# schematic.net
KiCad netlist of a schematic drawn in EAGLE
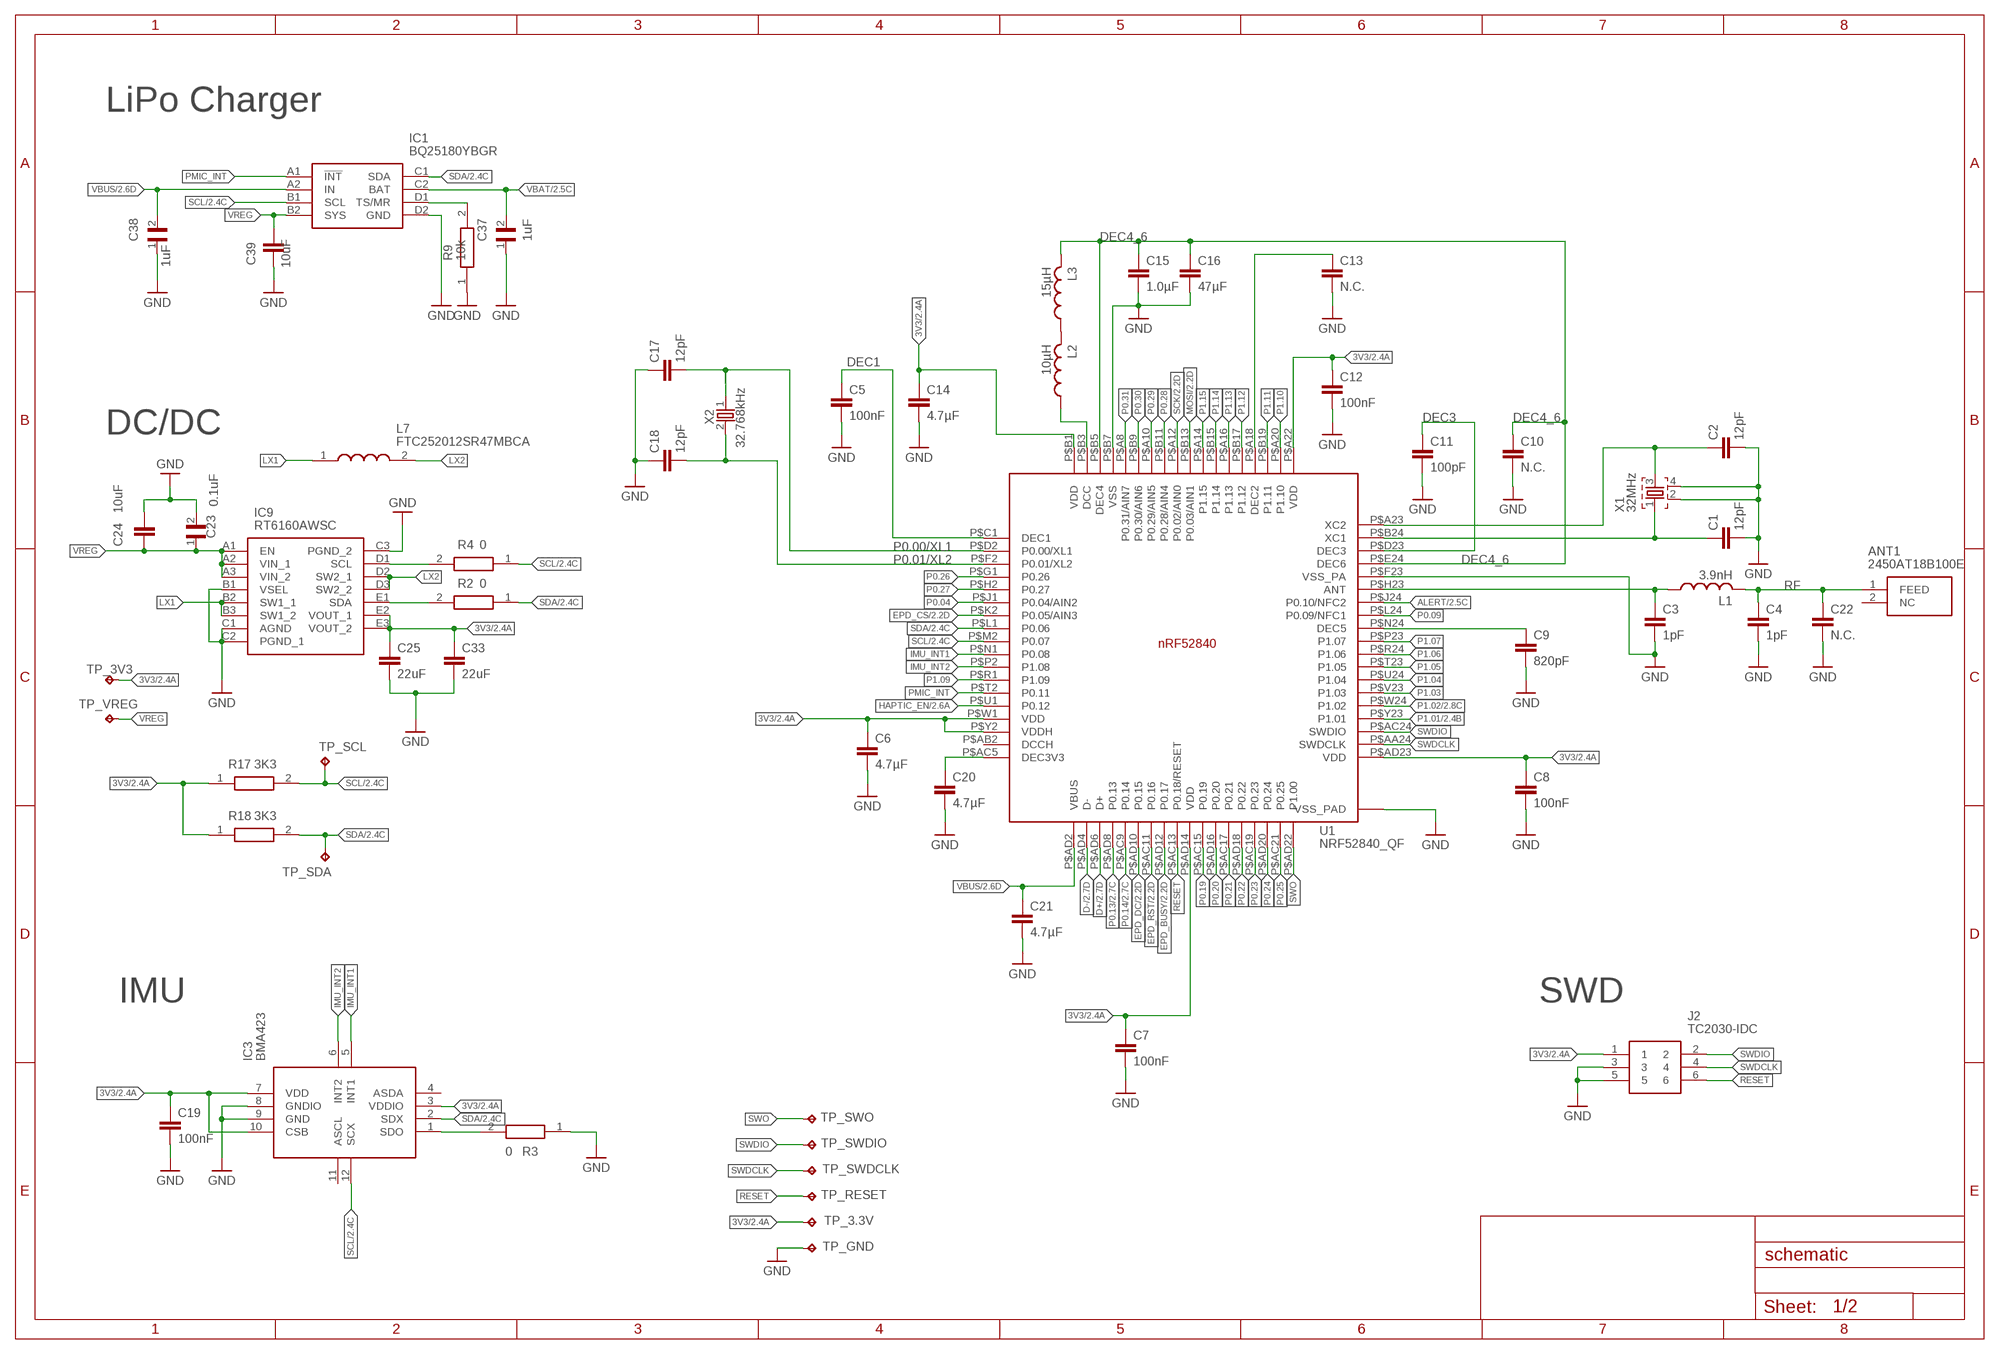
[diagram p0: schematic, sheet 1]
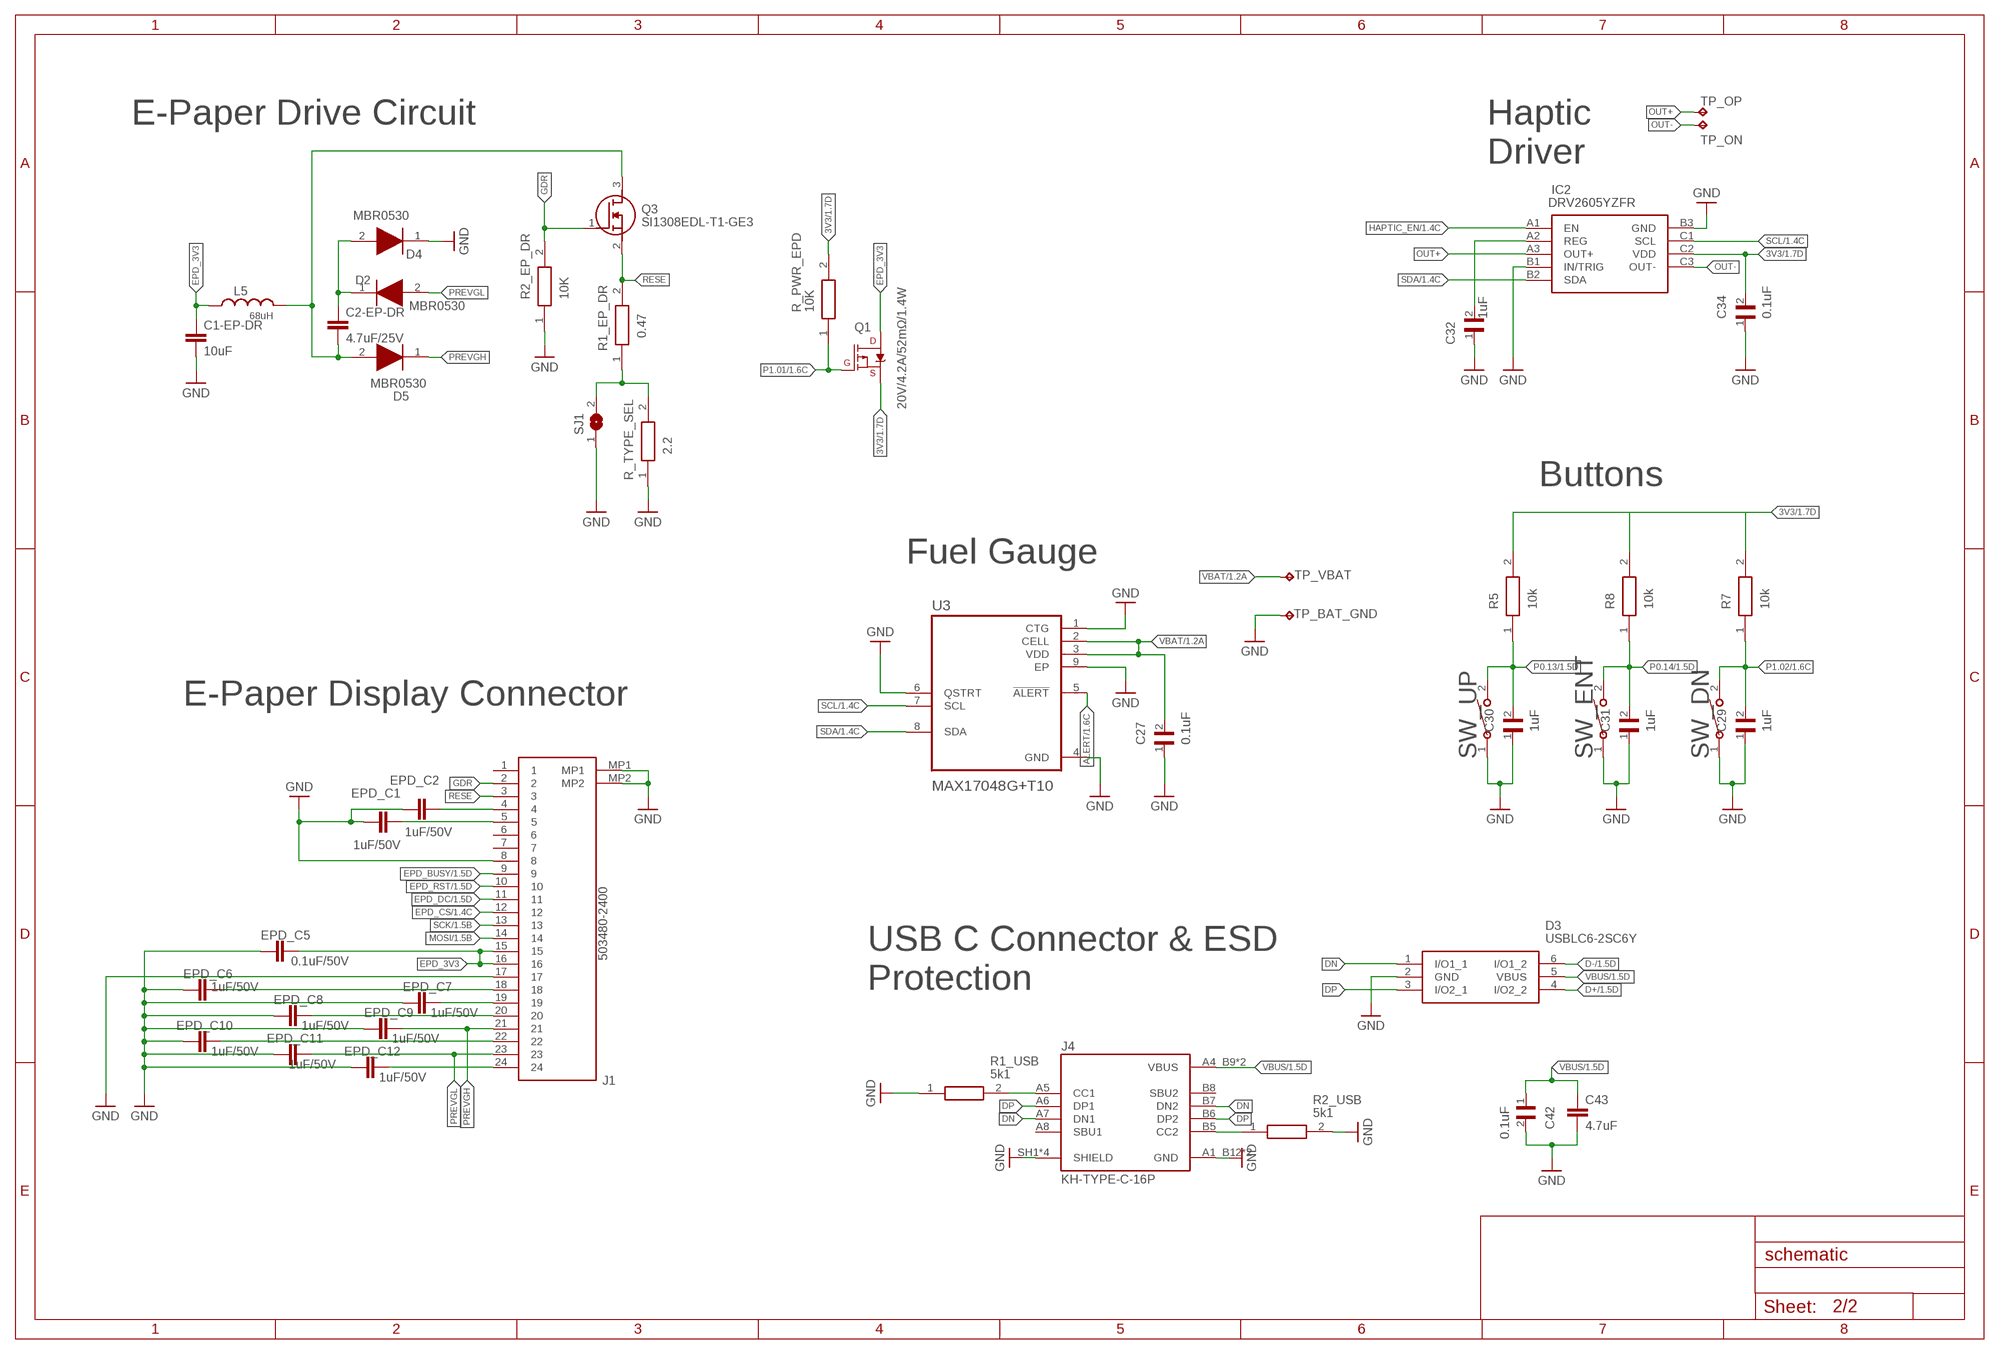
[diagram p1: schematic, sheet 2]

(export (version "E")
  (design (tool "Eeschema 10.0.6"))
  (components
    (comp (ref "ANT1")
      (value "2450AT18B100E")
      (footprint "eagle-import:2450AT18B100E_ANTC3216X140N")
      (fields (field (name "MOUSER_PART_NUMBER") "609-2450AT18B100E"))
      (libsource (lib "eagle-import") (part "2450AT18B100E_2450AT18B100E"))
    )
    (comp (ref "C1")
      (value "12pF")
      (footprint "eagle-import:NORDIC_NRF_3_RESC0201_L")
      (libsource (lib "eagle-import") (part "NORDIC_NRF_3_CAPACITOR_0201_L"))
    )
    (comp (ref "C2")
      (value "12pF")
      (footprint "eagle-import:NORDIC_NRF_3_RESC0201_L")
      (libsource (lib "eagle-import") (part "NORDIC_NRF_3_CAPACITOR_0201_L"))
    )
    (comp (ref "C3")
      (value "1pF")
      (footprint "eagle-import:NORDIC_NRF_3_RESC0201_L")
      (libsource (lib "eagle-import") (part "NORDIC_NRF_3_CAPACITOR_0201_L"))
    )
    (comp (ref "C4")
      (value "1pF")
      (footprint "eagle-import:NORDIC_NRF_3_RESC0201_L")
      (libsource (lib "eagle-import") (part "NORDIC_NRF_3_CAPACITOR_0201_L"))
    )
    (comp (ref "C5")
      (value "100nF")
      (footprint "eagle-import:NORDIC_NRF_3_RESC0201_L")
      (libsource (lib "eagle-import") (part "NORDIC_NRF_3_CAPACITOR_0201_L"))
    )
    (comp (ref "C6")
      (value "4.7µF")
      (footprint "eagle-import:NORDIC_NRF_3_RESC0402_L")
      (libsource (lib "eagle-import") (part "NORDIC_NRF_3_CAPACITOR_0402_L"))
    )
    (comp (ref "C7")
      (value "100nF")
      (footprint "eagle-import:NORDIC_NRF_3_RESC0201_L")
      (libsource (lib "eagle-import") (part "NORDIC_NRF_3_CAPACITOR_0201_L"))
    )
    (comp (ref "C8")
      (value "100nF")
      (footprint "eagle-import:NORDIC_NRF_3_RESC0201_L")
      (libsource (lib "eagle-import") (part "NORDIC_NRF_3_CAPACITOR_0201_L"))
    )
    (comp (ref "C9")
      (value "820pF")
      (footprint "eagle-import:NORDIC_NRF_3_RESC0201_L")
      (libsource (lib "eagle-import") (part "NORDIC_NRF_3_CAPACITOR_0201_L"))
    )
    (comp (ref "C10")
      (value "N.C.")
      (footprint "eagle-import:NORDIC_NRF_3_RESC0201_L")
      (libsource (lib "eagle-import") (part "NORDIC_NRF_3_CAPACITOR_0201_L"))
    )
    (comp (ref "C11")
      (value "100pF")
      (footprint "eagle-import:NORDIC_NRF_3_RESC0201_L")
      (libsource (lib "eagle-import") (part "NORDIC_NRF_3_CAPACITOR_0201_L"))
    )
    (comp (ref "C12")
      (value "100nF")
      (footprint "eagle-import:NORDIC_NRF_3_RESC0201_L")
      (libsource (lib "eagle-import") (part "NORDIC_NRF_3_CAPACITOR_0201_L"))
    )
    (comp (ref "C13")
      (value "N.C.")
      (footprint "eagle-import:NORDIC_NRF_3_RESC0201_L")
      (libsource (lib "eagle-import") (part "NORDIC_NRF_3_CAPACITOR_0201_L"))
    )
    (comp (ref "C14")
      (value "4.7µF")
      (footprint "eagle-import:NORDIC_NRF_3_RESC0402_L")
      (libsource (lib "eagle-import") (part "NORDIC_NRF_3_CAPACITOR_0402_L"))
    )
    (comp (ref "C15")
      (value "1.0µF")
      (footprint "eagle-import:NORDIC_NRF_3_RESC0402_L")
      (libsource (lib "eagle-import") (part "NORDIC_NRF_3_CAPACITOR_0402_L"))
    )
    (comp (ref "C16")
      (value "47µF")
      (footprint "eagle-import:NORDIC_NRF_3_RESC0402_L")
      (libsource (lib "eagle-import") (part "NORDIC_NRF_3_CAPACITOR_0402_L"))
    )
    (comp (ref "C17")
      (value "12pF")
      (footprint "eagle-import:NORDIC_NRF_3_RESC0201_L")
      (libsource (lib "eagle-import") (part "NORDIC_NRF_3_CAPACITOR_0201_L"))
    )
    (comp (ref "C18")
      (value "12pF")
      (footprint "eagle-import:NORDIC_NRF_3_RESC0201_L")
      (libsource (lib "eagle-import") (part "NORDIC_NRF_3_CAPACITOR_0201_L"))
    )
    (comp (ref "C19")
      (value "100nF")
      (footprint "eagle-import:NORDIC_NRF_3_RESC0201_L")
      (libsource (lib "eagle-import") (part "NORDIC_NRF_3_CAPACITOR_0201_L"))
    )
    (comp (ref "C20")
      (value "4.7µF")
      (footprint "eagle-import:NORDIC_NRF_3_RESC0402_L")
      (libsource (lib "eagle-import") (part "NORDIC_NRF_3_CAPACITOR_0402_L"))
    )
    (comp (ref "C21")
      (value "4.7µF")
      (footprint "eagle-import:NORDIC_NRF_3_RESC0402_L")
      (libsource (lib "eagle-import") (part "NORDIC_NRF_3_CAPACITOR_0402_L"))
    )
    (comp (ref "C22")
      (value "N.C.")
      (footprint "eagle-import:NORDIC_NRF_3_RESC0201_L")
      (libsource (lib "eagle-import") (part "NORDIC_NRF_3_CAPACITOR_0201_L"))
    )
    (comp (ref "C23")
      (value "0.1uF")
      (footprint "eagle-import:GRM011R60J152KE01L_2_CAPC0201X13N")
      (fields (field (name "MF") "Murata") (field (name "MP") "GRM011R60J152KE01L"))
      (libsource (lib "eagle-import") (part "GRM011R60J152KE01L_2_GRM011R60J152KE01L"))
    )
    (comp (ref "C24")
      (value "10uF")
      (footprint "eagle-import:NORDIC_NRF_3_RESC0402_L")
      (libsource (lib "eagle-import") (part "NORDIC_NRF_3_CAPACITOR_0402_L"))
    )
    (comp (ref "C25")
      (value "22uF")
      (footprint "eagle-import:NORDIC_NRF_3_RESC0402_L")
      (libsource (lib "eagle-import") (part "NORDIC_NRF_3_CAPACITOR_0402_L"))
    )
    (comp (ref "C33")
      (value "22uF")
      (footprint "eagle-import:NORDIC_NRF_3_RESC0402_L")
      (libsource (lib "eagle-import") (part "NORDIC_NRF_3_CAPACITOR_0402_L"))
    )
    (comp (ref "C37")
      (value "1uF")
      (footprint "eagle-import:GRM011R60J152KE01L_2_CAPC0201X13N")
      (fields (field (name "MF") "Murata") (field (name "MP") "GRM011R60J152KE01L"))
      (libsource (lib "eagle-import") (part "GRM011R60J152KE01L_2_GRM011R60J152KE01L"))
    )
    (comp (ref "C38")
      (value "1uF")
      (footprint "eagle-import:GRM011R60J152KE01L_2_CAPC0201X13N")
      (fields (field (name "MF") "Murata") (field (name "MP") "GRM011R60J152KE01L"))
      (libsource (lib "eagle-import") (part "GRM011R60J152KE01L_2_GRM011R60J152KE01L"))
    )
    (comp (ref "C39")
      (value "10uF")
      (footprint "eagle-import:NORDIC_NRF_3_RESC0402_L")
      (libsource (lib "eagle-import") (part "NORDIC_NRF_3_CAPACITOR_0402_L"))
    )
    (comp (ref "IC1")
      (value "BQ25180YBGR")
      (footprint "eagle-import:BQ25180YBGR_BGA8C40P2X4_100X155X50")
      (fields (field (name "MOUSER_PART_NUMBER") "595-BQ25180YBGR"))
      (libsource (lib "eagle-import") (part "BQ25180YBGR_BQ25180YBGR"))
    )
    (comp (ref "IC3")
      (value "BMA423")
      (footprint "eagle-import:BMA423_BMA423")
      (fields (field (name "MOUSER_PART_NUMBER") "262-BMA423"))
      (libsource (lib "eagle-import") (part "BMA423_BMA423"))
    )
    (comp (ref "IC9")
      (value "RT6160AWSC")
      (footprint "eagle-import:RT6160AWSC_BGA15C40P3X5_140X230X60")
      (fields (field (name "MOUSER_PART_NUMBER") "835-RT6160AWSC"))
      (libsource (lib "eagle-import") (part "RT6160AWSC_RT6160AWSC"))
    )
    (comp (ref "J2")
      (value "TC2030-IDC")
      (footprint "eagle-import:TC2030-IDC_TC2030IDC")
      (libsource (lib "eagle-import") (part "TC2030-IDC_TC2030-IDC"))
    )
    (comp (ref "L1")
      (value "3.9nH")
      (footprint "eagle-import:NORDIC_NRF_2_RESC0201_N")
      (libsource (lib "eagle-import") (part "NORDIC_NRF_2_INDUCTOR_0201_N"))
    )
    (comp (ref "L2")
      (value "10µH")
      (footprint "eagle-import:NORDIC_NRF_2_RESC0201_N")
      (libsource (lib "eagle-import") (part "NORDIC_NRF_2_INDUCTOR_0201_N"))
    )
    (comp (ref "L3")
      (value "15µH")
      (footprint "eagle-import:NORDIC_NRF_2_RESC0201_N")
      (libsource (lib "eagle-import") (part "NORDIC_NRF_2_INDUCTOR_0201_N"))
    )
    (comp (ref "L7")
      (value "FTC252012SR47MBCA")
      (footprint "eagle-import:MLP2016SR47MT0S1_INDC2016X100N")
      (libsource (lib "eagle-import") (part "MLP2016SR47MT0S1_FTC252012SR47MBCA"))
    )
    (comp (ref "R2")
      (value "0")
      (footprint "eagle-import:CPF0201D7K68C1_0201")
      (libsource (lib "eagle-import") (part "CPF0201D7K68C1_CPF0201D7K68C1"))
    )
    (comp (ref "R3")
      (value "0")
      (footprint "eagle-import:ERA-1AEB3401C_0201")
      (libsource (lib "eagle-import") (part "ERA-1AEB3401C_CPF0201D7K68C1"))
    )
    (comp (ref "R4")
      (value "0")
      (footprint "eagle-import:CPF0201D7K68C1_0201")
      (libsource (lib "eagle-import") (part "CPF0201D7K68C1_CPF0201D7K68C1"))
    )
    (comp (ref "R9")
      (value "10k")
      (footprint "eagle-import:CPF0201D7K68C1_0201")
      (libsource (lib "eagle-import") (part "CPF0201D7K68C1_CPF0201D7K68C1"))
    )
    (comp (ref "R17")
      (value "3K3")
      (footprint "eagle-import:ERA-1AEB3401C_0201")
      (libsource (lib "eagle-import") (part "ERA-1AEB3401C_CPF0201D7K68C1"))
    )
    (comp (ref "R18")
      (value "3K3")
      (footprint "eagle-import:ERA-1AEB3401C_0201")
      (libsource (lib "eagle-import") (part "ERA-1AEB3401C_CPF0201D7K68C1"))
    )
    (comp (ref "TP_3.3V")
      (value "HECTOR_WATCH_1_TPTP20R")
      (footprint "eagle-import:HECTOR_WATCH_1_TP20R")
      (libsource (lib "eagle-import") (part "HECTOR_WATCH_1_TPTP20R"))
    )
    (comp (ref "TP_3V3")
      (value "HECTOR_WATCH_1_TPTP20R")
      (footprint "eagle-import:HECTOR_WATCH_1_TP20R")
      (libsource (lib "eagle-import") (part "HECTOR_WATCH_1_TPTP20R"))
    )
    (comp (ref "TP_GND")
      (value "HECTOR_WATCH_1_TPTP20R")
      (footprint "eagle-import:HECTOR_WATCH_1_TP20R")
      (libsource (lib "eagle-import") (part "HECTOR_WATCH_1_TPTP20R"))
    )
    (comp (ref "TP_RESET")
      (value "HECTOR_WATCH_1_TPTP20R")
      (footprint "eagle-import:HECTOR_WATCH_1_TP20R")
      (libsource (lib "eagle-import") (part "HECTOR_WATCH_1_TPTP20R"))
    )
    (comp (ref "TP_SCL")
      (value "HECTOR_WATCH_1_TPTP20R")
      (footprint "eagle-import:HECTOR_WATCH_1_TP20R")
      (libsource (lib "eagle-import") (part "HECTOR_WATCH_1_TPTP20R"))
    )
    (comp (ref "TP_SDA")
      (value "HECTOR_WATCH_1_TPTP20R")
      (footprint "eagle-import:HECTOR_WATCH_1_TP20R")
      (libsource (lib "eagle-import") (part "HECTOR_WATCH_1_TPTP20R"))
    )
    (comp (ref "TP_SWDCLK")
      (value "HECTOR_WATCH_1_TPTP20R")
      (footprint "eagle-import:HECTOR_WATCH_1_TP20R")
      (libsource (lib "eagle-import") (part "HECTOR_WATCH_1_TPTP20R"))
    )
    (comp (ref "TP_SWDIO")
      (value "HECTOR_WATCH_1_TPTP20R")
      (footprint "eagle-import:HECTOR_WATCH_1_TP20R")
      (libsource (lib "eagle-import") (part "HECTOR_WATCH_1_TPTP20R"))
    )
    (comp (ref "TP_SWO")
      (value "HECTOR_WATCH_1_TPTP20R")
      (footprint "eagle-import:HECTOR_WATCH_1_TP20R")
      (libsource (lib "eagle-import") (part "HECTOR_WATCH_1_TPTP20R"))
    )
    (comp (ref "TP_VREG")
      (value "HECTOR_WATCH_1_TPTP20R")
      (footprint "eagle-import:HECTOR_WATCH_1_TP20R")
      (libsource (lib "eagle-import") (part "HECTOR_WATCH_1_TPTP20R"))
    )
    (comp (ref "U1")
      (value "NRF52840_QF")
      (footprint "eagle-import:NORDIC_NRF_4_AQFN50P700X700X85_HS-74N")
      (libsource (lib "eagle-import") (part "NORDIC_NRF_4_NRF52840_QF"))
    )
    (comp (ref "X1")
      (value "32MHz")
      (footprint "eagle-import:NORDIC_NRF_BT-XTAL_2016_N")
      (libsource (lib "eagle-import") (part "NORDIC_NRF_XTAL_32MHZ"))
    )
    (comp (ref "X2")
      (value "32.768kHz")
      (footprint "eagle-import:NORDIC_NRF_1_XTAL_3215_N")
      (libsource (lib "eagle-import") (part "NORDIC_NRF_1_XTAL_32KHZ"))
    )
    (comp (ref "C1-EP-DR")
      (value "10uF")
      (footprint "eagle-import:NORDIC_NRF_3_RESC0402_L")
      (libsource (lib "eagle-import") (part "NORDIC_NRF_3_CAPACITOR_0402_L"))
    )
    (comp (ref "C2-EP-DR")
      (value "4.7uF/25V")
      (footprint "eagle-import:NORDIC_NRF_3_RESC0402_L")
      (libsource (lib "eagle-import") (part "NORDIC_NRF_3_CAPACITOR_0402_L"))
    )
    (comp (ref "C27")
      (value "0.1uF")
      (footprint "eagle-import:GRM011R60J152KE01L_2_CAPC0201X13N")
      (fields (field (name "MF") "Murata") (field (name "MP") "GRM011R60J152KE01L"))
      (libsource (lib "eagle-import") (part "GRM011R60J152KE01L_2_GRM011R60J152KE01L"))
    )
    (comp (ref "C29")
      (value "1uF")
      (footprint "eagle-import:GRM011R60J152KE01L_2_CAPC0201X13N")
      (fields (field (name "MF") "Murata") (field (name "MP") "GRM011R60J152KE01L"))
      (libsource (lib "eagle-import") (part "GRM011R60J152KE01L_2_GRM011R60J152KE01L"))
    )
    (comp (ref "C30")
      (value "1uF")
      (footprint "eagle-import:GRM011R60J152KE01L_2_CAPC0201X13N")
      (fields (field (name "MF") "Murata") (field (name "MP") "GRM011R60J152KE01L"))
      (libsource (lib "eagle-import") (part "GRM011R60J152KE01L_2_GRM011R60J152KE01L"))
    )
    (comp (ref "C31")
      (value "1uF")
      (footprint "eagle-import:GRM011R60J152KE01L_2_CAPC0201X13N")
      (fields (field (name "MF") "Murata") (field (name "MP") "GRM011R60J152KE01L"))
      (libsource (lib "eagle-import") (part "GRM011R60J152KE01L_2_GRM011R60J152KE01L"))
    )
    (comp (ref "C32")
      (value "1uF")
      (footprint "eagle-import:GRM011R60J152KE01L_2_CAPC0201X13N")
      (fields (field (name "MF") "Murata") (field (name "MP") "GRM011R60J152KE01L"))
      (libsource (lib "eagle-import") (part "GRM011R60J152KE01L_2_GRM011R60J152KE01L"))
    )
    (comp (ref "C34")
      (value "0.1uF")
      (footprint "eagle-import:GRM011R60J152KE01L_2_CAPC0201X13N")
      (fields (field (name "MF") "Murata") (field (name "MP") "GRM011R60J152KE01L"))
      (libsource (lib "eagle-import") (part "GRM011R60J152KE01L_2_GRM011R60J152KE01L"))
    )
    (comp (ref "C42")
      (value "0.1uF")
      (footprint "eagle-import:GRM011R60J152KE01L_2_CAPC0201X13N")
      (fields (field (name "MF") "Murata") (field (name "MP") "GRM011R60J152KE01L"))
      (libsource (lib "eagle-import") (part "GRM011R60J152KE01L_2_GRM011R60J152KE01L"))
    )
    (comp (ref "C43")
      (value "4.7uF")
      (footprint "eagle-import:NORDIC_NRF_3_RESC0402_L")
      (libsource (lib "eagle-import") (part "NORDIC_NRF_3_CAPACITOR_0402_L"))
    )
    (comp (ref "D2")
      (value "MBR0530")
      (footprint "eagle-import:ESP32_C6_LIBRARY_5_SOD3716X135N")
      (fields (field (name "MF") "ON Semiconductor"))
      (libsource (lib "eagle-import") (part "ESP32_C6_LIBRARY_5_MBR0530"))
    )
    (comp (ref "D3")
      (value "USBLC6-2SC6Y")
      (footprint "eagle-import:ESP32_C6_LIBRARY_3_SOT95P280X145-6N")
      (fields (field (name "MF") "STMicroelectronics"))
      (libsource (lib "eagle-import") (part "ESP32_C6_LIBRARY_3_USBLC6-2SC6Y"))
    )
    (comp (ref "D4")
      (value "MBR0530")
      (footprint "eagle-import:ESP32_C6_LIBRARY_5_SOD3716X135N")
      (fields (field (name "MF") "ON Semiconductor"))
      (libsource (lib "eagle-import") (part "ESP32_C6_LIBRARY_5_MBR0530"))
    )
    (comp (ref "D5")
      (value "MBR0530")
      (footprint "eagle-import:ESP32_C6_LIBRARY_5_SOD3716X135N")
      (fields (field (name "MF") "ON Semiconductor"))
      (libsource (lib "eagle-import") (part "ESP32_C6_LIBRARY_5_MBR0530"))
    )
    (comp (ref "EPD_C1")
      (value "1uF/50V")
      (footprint "eagle-import:NORDIC_NRF_3_RESC0201_L")
      (libsource (lib "eagle-import") (part "NORDIC_NRF_3_CAPACITOR_0201_L"))
    )
    (comp (ref "EPD_C2")
      (value "1uF/50V")
      (footprint "eagle-import:NORDIC_NRF_3_RESC0201_L")
      (libsource (lib "eagle-import") (part "NORDIC_NRF_3_CAPACITOR_0201_L"))
    )
    (comp (ref "EPD_C5")
      (value "0.1uF/50V")
      (footprint "eagle-import:NORDIC_NRF_3_RESC0201_L")
      (libsource (lib "eagle-import") (part "NORDIC_NRF_3_CAPACITOR_0201_L"))
    )
    (comp (ref "EPD_C6")
      (value "1uF/50V")
      (footprint "eagle-import:NORDIC_NRF_3_RESC0402_L")
      (libsource (lib "eagle-import") (part "NORDIC_NRF_3_CAPACITOR_0402_L"))
    )
    (comp (ref "EPD_C7")
      (value "1uF/50V")
      (footprint "eagle-import:NORDIC_NRF_3_RESC0402_L")
      (libsource (lib "eagle-import") (part "NORDIC_NRF_3_CAPACITOR_0402_L"))
    )
    (comp (ref "EPD_C8")
      (value "1uF/50V")
      (footprint "eagle-import:NORDIC_NRF_3_RESC0402_L")
      (libsource (lib "eagle-import") (part "NORDIC_NRF_3_CAPACITOR_0402_L"))
    )
    (comp (ref "EPD_C9")
      (value "1uF/50V")
      (footprint "eagle-import:NORDIC_NRF_3_RESC0402_L")
      (libsource (lib "eagle-import") (part "NORDIC_NRF_3_CAPACITOR_0402_L"))
    )
    (comp (ref "EPD_C10")
      (value "1uF/50V")
      (footprint "eagle-import:NORDIC_NRF_3_RESC0402_L")
      (libsource (lib "eagle-import") (part "NORDIC_NRF_3_CAPACITOR_0402_L"))
    )
    (comp (ref "EPD_C11")
      (value "1uF/50V")
      (footprint "eagle-import:NORDIC_NRF_3_RESC0402_L")
      (libsource (lib "eagle-import") (part "NORDIC_NRF_3_CAPACITOR_0402_L"))
    )
    (comp (ref "EPD_C12")
      (value "1uF/50V")
      (footprint "eagle-import:NORDIC_NRF_3_RESC0402_L")
      (libsource (lib "eagle-import") (part "NORDIC_NRF_3_CAPACITOR_0402_L"))
    )
    (comp (ref "IC2")
      (value "DRV2605YZFR")
      (footprint "eagle-import:DRV2605YZFR_BGA9C50P3X3_144X144X62")
      (libsource (lib "eagle-import") (part "DRV2605YZFR_DRV2605YZFR"))
    )
    (comp (ref "J1")
      (value "503480-2400")
      (footprint "eagle-import:503480-2400_5034802400")
      (fields (field (name "MOUSER_PART_NUMBER") "538-503480-2400"))
      (libsource (lib "eagle-import") (part "503480-2400_503480-2400"))
    )
    (comp (ref "J4")
      (value "KH-TYPE-C-16P")
      (footprint "eagle-import:KH-TYPE-C-16P_KINGHELM_KH-TYPE-C-16P")
      (fields (field (name "MF") "kinghelm"))
      (libsource (lib "eagle-import") (part "KH-TYPE-C-16P_KH-TYPE-C-16P"))
    )
    (comp (ref "L5")
      (value "68uH")
      (footprint "eagle-import:NORDIC_NRF_2_RESC0201_N")
      (libsource (lib "eagle-import") (part "NORDIC_NRF_2_INDUCTOR_0201_N"))
    )
    (comp (ref "Q1")
      (value "20V/4.2A/52mΩ/1.4W")
      (footprint "eagle-import:ESP32_C6_LIBRARY_4_ESP32_C6_LIBRARY_4_ESP32_C6_LIBRARY_4_ESP32_C6_LIBRARY_4_ESP32_WROVER_SPARKFUN-DISCRETESEMI_SOT23-3")
      (libsource (lib "eagle-import") (part "ESP32_C6_LIBRARY_4_ESP32_WROVER_SPARKFUN-DISCRETESEMI_MOSFET_PCH-DMG2305UX-7"))
    )
    (comp (ref "Q3")
      (value "SI1308EDL-T1-GE3")
      (footprint "eagle-import:ESP32_C6_LIBRARY_6_SOT65P210X110-3N")
      (fields (field (name "MF") "Vishay Siliconix"))
      (libsource (lib "eagle-import") (part "ESP32_C6_LIBRARY_6_SI1308EDL-T1-GE3"))
    )
    (comp (ref "R1_EP_DR")
      (value "0.47")
      (footprint "eagle-import:CPF0201D7K68C1_0201")
      (libsource (lib "eagle-import") (part "CPF0201D7K68C1_CPF0201D7K68C1"))
    )
    (comp (ref "R1_USB")
      (value "5k1")
      (footprint "eagle-import:ERA-1AEB3401C_0201")
      (libsource (lib "eagle-import") (part "ERA-1AEB3401C_CPF0201D7K68C1"))
    )
    (comp (ref "R2_EP_DR")
      (value "10K")
      (footprint "eagle-import:CPF0201D7K68C1_0201")
      (libsource (lib "eagle-import") (part "CPF0201D7K68C1_CPF0201D7K68C1"))
    )
    (comp (ref "R2_USB")
      (value "5k1")
      (footprint "eagle-import:ERA-1AEB3401C_0201")
      (libsource (lib "eagle-import") (part "ERA-1AEB3401C_CPF0201D7K68C1"))
    )
    (comp (ref "R5")
      (value "10k")
      (footprint "eagle-import:CPF0201D7K68C1_0201")
      (libsource (lib "eagle-import") (part "CPF0201D7K68C1_CPF0201D7K68C1"))
    )
    (comp (ref "R7")
      (value "10k")
      (footprint "eagle-import:CPF0201D7K68C1_0201")
      (libsource (lib "eagle-import") (part "CPF0201D7K68C1_CPF0201D7K68C1"))
    )
    (comp (ref "R8")
      (value "10k")
      (footprint "eagle-import:CPF0201D7K68C1_0201")
      (libsource (lib "eagle-import") (part "CPF0201D7K68C1_CPF0201D7K68C1"))
    )
    (comp (ref "R_PWR_EPD")
      (value "10K")
      (footprint "eagle-import:CPF0201D7K68C1_0201")
      (libsource (lib "eagle-import") (part "CPF0201D7K68C1_CPF0201D7K68C1"))
    )
    (comp (ref "R_TYPE_SEL")
      (value "2.2")
      (footprint "eagle-import:CPF0201D7K68C1_0201")
      (libsource (lib "eagle-import") (part "CPF0201D7K68C1_CPF0201D7K68C1"))
    )
    (comp (ref "SJ1")
      (value "ESP32_C6_LIBRARY_7_JUMPER_SJ")
      (footprint "eagle-import:ESP32_C6_LIBRARY_7_JUMPER_SJ")
      (libsource (lib "eagle-import") (part "ESP32_C6_LIBRARY_7_JUMPER_SJ"))
    )
    (comp (ref "SW_DN")
      (value "2025-10-22_07-23-44_LIBRARY_EVP-AKE31ASW_EVP-AKE31A_PAN")
      (footprint "eagle-import:2025-10-22_07-23-44_LIBRARY_SW_EVP-AKE31A_PAN")
      (fields
        (field (name "MANUFACTURER_PART_NUMBER") "EVP-AKE31A")
        (field (name "COPYRIGHT") "Copyright (C) 2025 Ultra Librarian. All rights reserved.")
      )
      (libsource (lib "eagle-import") (part "2025-10-22_07-23-44_LIBRARY_EVP-AKE31ASW_EVP-AKE31A_PAN"))
    )
    (comp (ref "SW_ENT")
      (value "2025-10-22_07-23-44_LIBRARY_EVP-AKE31ASW_EVP-AKE31A_PAN")
      (footprint "eagle-import:2025-10-22_07-23-44_LIBRARY_SW_EVP-AKE31A_PAN")
      (fields
        (field (name "MANUFACTURER_PART_NUMBER") "EVP-AKE31A")
        (field (name "COPYRIGHT") "Copyright (C) 2025 Ultra Librarian. All rights reserved.")
      )
      (libsource (lib "eagle-import") (part "2025-10-22_07-23-44_LIBRARY_EVP-AKE31ASW_EVP-AKE31A_PAN"))
    )
    (comp (ref "SW_UP")
      (value "2025-10-22_07-23-44_LIBRARY_EVP-AKE31ASW_EVP-AKE31A_PAN")
      (footprint "eagle-import:2025-10-22_07-23-44_LIBRARY_SW_EVP-AKE31A_PAN")
      (fields
        (field (name "MANUFACTURER_PART_NUMBER") "EVP-AKE31A")
        (field (name "COPYRIGHT") "Copyright (C) 2025 Ultra Librarian. All rights reserved.")
      )
      (libsource (lib "eagle-import") (part "2025-10-22_07-23-44_LIBRARY_EVP-AKE31ASW_EVP-AKE31A_PAN"))
    )
    (comp (ref "TP_BAT_GND")
      (value "HECTOR_WATCH_1_TPTP20R")
      (footprint "eagle-import:HECTOR_WATCH_1_TP20R")
      (libsource (lib "eagle-import") (part "HECTOR_WATCH_1_TPTP20R"))
    )
    (comp (ref "TP_ON")
      (value "HECTOR_WATCH_1_TPTP20R")
      (footprint "eagle-import:HECTOR_WATCH_1_TP20R")
      (libsource (lib "eagle-import") (part "HECTOR_WATCH_1_TPTP20R"))
    )
    (comp (ref "TP_OP")
      (value "HECTOR_WATCH_1_TPTP20R")
      (footprint "eagle-import:HECTOR_WATCH_1_TP20R")
      (libsource (lib "eagle-import") (part "HECTOR_WATCH_1_TPTP20R"))
    )
    (comp (ref "TP_VBAT")
      (value "HECTOR_WATCH_1_TPTP20R")
      (footprint "eagle-import:HECTOR_WATCH_1_TP20R")
      (libsource (lib "eagle-import") (part "HECTOR_WATCH_1_TPTP20R"))
    )
    (comp (ref "U3")
      (value "MAX17048G+T10")
      (footprint "eagle-import:ESP32_C6_LIBRARY_SON50P200X200X80-9N")
      (fields (field (name "MF") "Analog Devices"))
      (libsource (lib "eagle-import") (part "ESP32_C6_LIBRARY_MAX17048G+T10"))
    )
  )
  (nets
    (net (code "1") (name "3V3{slash}1.7D") (class "Default")
      (node (ref "C34") (pin "2") (pinfunction "2_2") (pintype "passive"))
      (node (ref "IC2") (pin "C2") (pinfunction "VDD_C2") (pintype "bidirectional"))
      (node (ref "Q1") (pin "2") (pinfunction "S_2") (pintype "bidirectional"))
      (node (ref "R5") (pin "2") (pinfunction "2_2") (pintype "bidirectional"))
      (node (ref "R_PWR_EPD") (pin "2") (pinfunction "2_2") (pintype "bidirectional"))
    )
    (net (code "2") (name "3V3{slash}2.4A") (class "Default")
      (node (ref "C12") (pin "1") (pinfunction "1_1") (pintype "passive"))
      (node (ref "C14") (pin "1") (pinfunction "1_1") (pintype "passive"))
      (node (ref "C19") (pin "1") (pinfunction "1_1") (pintype "passive"))
      (node (ref "C25") (pin "1") (pinfunction "1_1") (pintype "passive"))
      (node (ref "C33") (pin "1") (pinfunction "1_1") (pintype "passive"))
      (node (ref "C6") (pin "1") (pinfunction "1_1") (pintype "passive"))
      (node (ref "C7") (pin "1") (pinfunction "1_1") (pintype "passive"))
      (node (ref "C8") (pin "1") (pinfunction "1_1") (pintype "passive"))
      (node (ref "IC3") (pin "10") (pinfunction "CSB_10") (pintype "bidirectional"))
      (node (ref "IC3") (pin "3") (pinfunction "VDDIO_3") (pintype "bidirectional"))
      (node (ref "IC3") (pin "7") (pinfunction "VDD_7") (pintype "bidirectional"))
      (node (ref "IC9") (pin "E2") (pinfunction "VOUT_1_E2") (pintype "bidirectional"))
      (node (ref "IC9") (pin "E3") (pinfunction "VOUT_2_E3") (pintype "bidirectional"))
      (node (ref "J2") (pin "1") (pinfunction "1_1") (pintype "bidirectional"))
      (node (ref "R17") (pin "1") (pinfunction "1_1") (pintype "bidirectional"))
      (node (ref "R18") (pin "1") (pinfunction "1_1") (pintype "bidirectional"))
      (node (ref "TP_3.3V") (pin "TP") (pinfunction "TP_TP") (pintype "input"))
      (node (ref "TP_3V3") (pin "TP") (pinfunction "TP_TP") (pintype "input"))
      (node (ref "U1") (pin "P$A22") (pinfunction "VDD_P$A22") (pintype "power_in"))
      (node (ref "U1") (pin "P$AD14") (pinfunction "VDD_P$AD14") (pintype "power_in"))
      (node (ref "U1") (pin "P$AD23") (pinfunction "VDD_P$AD23") (pintype "power_in"))
      (node (ref "U1") (pin "P$B1") (pinfunction "VDD_P$B1") (pintype "power_in"))
      (node (ref "U1") (pin "P$W1") (pinfunction "VDD_P$W1") (pintype "power_in"))
      (node (ref "U1") (pin "P$Y2") (pinfunction "VDDH_P$Y2") (pintype "power_in"))
    )
    (net (code "3") (name "ALERT") (class "Default")
      (node (ref "U1") (pin "P$J24") (pinfunction "P0.10/NFC2_P$J24") (pintype "bidirectional"))
      (node (ref "U3") (pin "5") (pinfunction "~{ALERT}_5") (pintype "output"))
    )
    (net (code "4") (name "D+") (class "Default")
      (node (ref "D3") (pin "4") (pinfunction "I/O2_2_4") (pintype "bidirectional"))
      (node (ref "U1") (pin "P$AD6") (pinfunction "D+_P$AD6") (pintype "bidirectional"))
    )
    (net (code "5") (name "D-") (class "Default")
      (node (ref "D3") (pin "6") (pinfunction "I/O1_2_6") (pintype "bidirectional"))
      (node (ref "U1") (pin "P$AD4") (pinfunction "D-_P$AD4") (pintype "bidirectional"))
    )
    (net (code "6") (name "DEC1") (class "Default")
      (node (ref "C5") (pin "1") (pinfunction "1_1") (pintype "passive"))
      (node (ref "U1") (pin "P$C1") (pinfunction "DEC1_P$C1") (pintype "power_in"))
    )
    (net (code "7") (name "DEC3") (class "Default")
      (node (ref "C11") (pin "1") (pinfunction "1_1") (pintype "passive"))
      (node (ref "U1") (pin "P$D23") (pinfunction "DEC3_P$D23") (pintype "bidirectional"))
    )
    (net (code "8") (name "DEC4_6") (class "Default")
      (node (ref "C10") (pin "1") (pinfunction "1_1") (pintype "passive"))
      (node (ref "C15") (pin "1") (pinfunction "1_1") (pintype "passive"))
      (node (ref "C16") (pin "1") (pinfunction "1_1") (pintype "passive"))
      (node (ref "L3") (pin "2") (pinfunction "2_2") (pintype "passive"))
      (node (ref "U1") (pin "P$B5") (pinfunction "DEC4_P$B5") (pintype "power_in"))
      (node (ref "U1") (pin "P$E24") (pinfunction "DEC6_P$E24") (pintype "bidirectional"))
    )
    (net (code "9") (name "DN") (class "Default")
      (node (ref "D3") (pin "1") (pinfunction "I/O1_1_1") (pintype "bidirectional"))
      (node (ref "J4") (pin "A7") (pinfunction "DN1_A7") (pintype "bidirectional"))
      (node (ref "J4") (pin "B7") (pinfunction "DN2_B7") (pintype "bidirectional"))
    )
    (net (code "10") (name "DP") (class "Default")
      (node (ref "D3") (pin "3") (pinfunction "I/O2_1_3") (pintype "bidirectional"))
      (node (ref "J4") (pin "A6") (pinfunction "DP1_A6") (pintype "bidirectional"))
      (node (ref "J4") (pin "B6") (pinfunction "DP2_B6") (pintype "bidirectional"))
    )
    (net (code "11") (name "EPD_3V3") (class "Default")
      (node (ref "C1-EP-DR") (pin "1") (pinfunction "1_1") (pintype "passive"))
      (node (ref "EPD_C5") (pin "2") (pinfunction "2_2") (pintype "passive"))
      (node (ref "J1") (pin "15") (pinfunction "15_15") (pintype "bidirectional"))
      (node (ref "J1") (pin "16") (pinfunction "16_16") (pintype "bidirectional"))
      (node (ref "L5") (pin "1") (pinfunction "1_1") (pintype "passive"))
      (node (ref "Q1") (pin "3") (pinfunction "D_3") (pintype "bidirectional"))
    )
    (net (code "12") (name "EPD_BUSY") (class "Default")
      (node (ref "J1") (pin "9") (pinfunction "9_9") (pintype "bidirectional"))
      (node (ref "U1") (pin "P$AD12") (pinfunction "P0.17_P$AD12") (pintype "bidirectional"))
    )
    (net (code "13") (name "EPD_CS") (class "Default")
      (node (ref "J1") (pin "12") (pinfunction "12_12") (pintype "bidirectional"))
      (node (ref "U1") (pin "P$K2") (pinfunction "P0.05/AIN3_P$K2") (pintype "bidirectional"))
    )
    (net (code "14") (name "EPD_DC") (class "Default")
      (node (ref "J1") (pin "11") (pinfunction "11_11") (pintype "bidirectional"))
      (node (ref "U1") (pin "P$AD10") (pinfunction "P0.15_P$AD10") (pintype "bidirectional"))
    )
    (net (code "15") (name "EPD_RST") (class "Default")
      (node (ref "J1") (pin "10") (pinfunction "10_10") (pintype "bidirectional"))
      (node (ref "U1") (pin "P$AC11") (pinfunction "P0.16_P$AC11") (pintype "bidirectional"))
    )
    (net (code "16") (name "GDR") (class "Default")
      (node (ref "J1") (pin "2") (pinfunction "2_2") (pintype "bidirectional"))
      (node (ref "Q3") (pin "1") (pinfunction "G_1") (pintype "bidirectional"))
      (node (ref "R2_EP_DR") (pin "2") (pinfunction "2_2") (pintype "bidirectional"))
    )
    (net (code "17") (name "GND") (class "Default")
      (node (ref "C1") (pin "2") (pinfunction "2_2") (pintype "passive"))
      (node (ref "C1-EP-DR") (pin "2") (pinfunction "2_2") (pintype "passive"))
      (node (ref "C10") (pin "2") (pinfunction "2_2") (pintype "passive"))
      (node (ref "C11") (pin "2") (pinfunction "2_2") (pintype "passive"))
      (node (ref "C12") (pin "2") (pinfunction "2_2") (pintype "passive"))
      (node (ref "C13") (pin "2") (pinfunction "2_2") (pintype "passive"))
      (node (ref "C14") (pin "2") (pinfunction "2_2") (pintype "passive"))
      (node (ref "C15") (pin "2") (pinfunction "2_2") (pintype "passive"))
      (node (ref "C16") (pin "2") (pinfunction "2_2") (pintype "passive"))
      (node (ref "C17") (pin "1") (pinfunction "1_1") (pintype "passive"))
      (node (ref "C18") (pin "1") (pinfunction "1_1") (pintype "passive"))
      (node (ref "C19") (pin "2") (pinfunction "2_2") (pintype "passive"))
      (node (ref "C2") (pin "2") (pinfunction "2_2") (pintype "passive"))
      (node (ref "C20") (pin "2") (pinfunction "2_2") (pintype "passive"))
      (node (ref "C21") (pin "2") (pinfunction "2_2") (pintype "passive"))
      (node (ref "C22") (pin "2") (pinfunction "2_2") (pintype "passive"))
      (node (ref "C23") (pin "2") (pinfunction "2_2") (pintype "passive"))
      (node (ref "C24") (pin "1") (pinfunction "1_1") (pintype "passive"))
      (node (ref "C25") (pin "2") (pinfunction "2_2") (pintype "passive"))
      (node (ref "C27") (pin "1") (pinfunction "1_1") (pintype "passive"))
      (node (ref "C29") (pin "1") (pinfunction "1_1") (pintype "passive"))
      (node (ref "C3") (pin "2") (pinfunction "2_2") (pintype "passive"))
      (node (ref "C30") (pin "1") (pinfunction "1_1") (pintype "passive"))
      (node (ref "C31") (pin "1") (pinfunction "1_1") (pintype "passive"))
      (node (ref "C32") (pin "1") (pinfunction "1_1") (pintype "passive"))
      (node (ref "C33") (pin "2") (pinfunction "2_2") (pintype "passive"))
      (node (ref "C34") (pin "1") (pinfunction "1_1") (pintype "passive"))
      (node (ref "C37") (pin "1") (pinfunction "1_1") (pintype "passive"))
      (node (ref "C38") (pin "1") (pinfunction "1_1") (pintype "passive"))
      (node (ref "C39") (pin "2") (pinfunction "2_2") (pintype "passive"))
      (node (ref "C4") (pin "2") (pinfunction "2_2") (pintype "passive"))
      (node (ref "C42") (pin "2") (pinfunction "2_2") (pintype "passive"))
      (node (ref "C43") (pin "2") (pinfunction "2_2") (pintype "passive"))
      (node (ref "C5") (pin "2") (pinfunction "2_2") (pintype "passive"))
      (node (ref "C6") (pin "2") (pinfunction "2_2") (pintype "passive"))
      (node (ref "C7") (pin "2") (pinfunction "2_2") (pintype "passive"))
      (node (ref "C8") (pin "2") (pinfunction "2_2") (pintype "passive"))
      (node (ref "C9") (pin "2") (pinfunction "2_2") (pintype "passive"))
      (node (ref "D3") (pin "2") (pinfunction "GND_2") (pintype "bidirectional"))
      (node (ref "D4") (pin "1") (pinfunction "K_1") (pintype "bidirectional"))
      (node (ref "EPD_C1") (pin "1") (pinfunction "1_1") (pintype "passive"))
      (node (ref "EPD_C10") (pin "1") (pinfunction "1_1") (pintype "passive"))
      (node (ref "EPD_C11") (pin "1") (pinfunction "1_1") (pintype "passive"))
      (node (ref "EPD_C12") (pin "1") (pinfunction "1_1") (pintype "passive"))
      (node (ref "EPD_C2") (pin "1") (pinfunction "1_1") (pintype "passive"))
      (node (ref "EPD_C5") (pin "1") (pinfunction "1_1") (pintype "passive"))
      (node (ref "EPD_C6") (pin "1") (pinfunction "1_1") (pintype "passive"))
      (node (ref "EPD_C7") (pin "1") (pinfunction "1_1") (pintype "passive"))
      (node (ref "EPD_C8") (pin "1") (pinfunction "1_1") (pintype "passive"))
      (node (ref "EPD_C9") (pin "1") (pinfunction "1_1") (pintype "passive"))
      (node (ref "IC1") (pin "D2") (pinfunction "GND_D2") (pintype "bidirectional"))
      (node (ref "IC2") (pin "B1") (pinfunction "IN/TRIG_B1") (pintype "bidirectional"))
      (node (ref "IC2") (pin "B3") (pinfunction "GND_B3") (pintype "bidirectional"))
      (node (ref "IC3") (pin "8") (pinfunction "GNDIO_8") (pintype "bidirectional"))
      (node (ref "IC3") (pin "9") (pinfunction "GND_9") (pintype "bidirectional"))
      (node (ref "IC9") (pin "B1") (pinfunction "VSEL_B1") (pintype "bidirectional"))
      (node (ref "IC9") (pin "C1") (pinfunction "AGND_C1") (pintype "bidirectional"))
      (node (ref "IC9") (pin "C2") (pinfunction "PGND_1_C2") (pintype "bidirectional"))
      (node (ref "IC9") (pin "C3") (pinfunction "PGND_2_C3") (pintype "bidirectional"))
      (node (ref "J1") (pin "17") (pinfunction "17_17") (pintype "bidirectional"))
      (node (ref "J1") (pin "8") (pinfunction "8_8") (pintype "bidirectional"))
      (node (ref "J1") (pin "MP1") (pinfunction "MP1_MP1") (pintype "bidirectional"))
      (node (ref "J1") (pin "MP2") (pinfunction "MP2_MP2") (pintype "bidirectional"))
      (node (ref "J2") (pin "3") (pinfunction "3_3") (pintype "bidirectional"))
      (node (ref "J2") (pin "5") (pinfunction "5_5") (pintype "bidirectional"))
      (node (ref "J4") (pin "A12_B1") (pinfunction "GND_A12_B1") (pintype "power_in"))
      (node (ref "J4") (pin "A1_B12") (pinfunction "GND_A1_B12") (pintype "power_in"))
      (node (ref "J4") (pin "SH1") (pinfunction "SHIELD_SH1") (pintype "passive"))
      (node (ref "J4") (pin "SH2") (pinfunction "SHIELD_SH2") (pintype "passive"))
      (node (ref "J4") (pin "SH3") (pinfunction "SHIELD_SH3") (pintype "passive"))
      (node (ref "J4") (pin "SH4") (pinfunction "SHIELD_SH4") (pintype "passive"))
      (node (ref "R1_USB") (pin "1") (pinfunction "1_1") (pintype "bidirectional"))
      (node (ref "R2_EP_DR") (pin "1") (pinfunction "1_1") (pintype "bidirectional"))
      (node (ref "R2_USB") (pin "2") (pinfunction "2_2") (pintype "bidirectional"))
      (node (ref "R3") (pin "1") (pinfunction "1_1") (pintype "bidirectional"))
      (node (ref "R9") (pin "1") (pinfunction "1_1") (pintype "bidirectional"))
      (node (ref "R_TYPE_SEL") (pin "1") (pinfunction "1_1") (pintype "bidirectional"))
      (node (ref "SJ1") (pin "1") (pinfunction "1_1") (pintype "passive"))
      (node (ref "SW_DN") (pin "1") (pinfunction "1_1") (pintype "passive"))
      (node (ref "SW_ENT") (pin "1") (pinfunction "1_1") (pintype "passive"))
      (node (ref "SW_UP") (pin "1") (pinfunction "1_1") (pintype "passive"))
      (node (ref "TP_BAT_GND") (pin "TP") (pinfunction "TP_TP") (pintype "input"))
      (node (ref "TP_GND") (pin "TP") (pinfunction "TP_TP") (pintype "input"))
      (node (ref "U1") (pin "P$74") (pinfunction "VSS_PAD_P$74") (pintype "bidirectional"))
      (node (ref "U1") (pin "P$75") (pinfunction "VSS_PAD_P$75") (pintype "bidirectional"))
      (node (ref "U1") (pin "P$76") (pinfunction "VSS_PAD_P$76") (pintype "bidirectional"))
      (node (ref "U1") (pin "P$77") (pinfunction "VSS_PAD_P$77") (pintype "bidirectional"))
      (node (ref "U1") (pin "P$78") (pinfunction "VSS_PAD_P$78") (pintype "bidirectional"))
      (node (ref "U1") (pin "P$79") (pinfunction "VSS_PAD_P$79") (pintype "bidirectional"))
      (node (ref "U1") (pin "P$80") (pinfunction "VSS_PAD_P$80") (pintype "bidirectional"))
      (node (ref "U1") (pin "P$81") (pinfunction "VSS_PAD_P$81") (pintype "bidirectional"))
      (node (ref "U1") (pin "P$82") (pinfunction "VSS_PAD_P$82") (pintype "bidirectional"))
      (node (ref "U1") (pin "P$83") (pinfunction "VSS_PAD_P$83") (pintype "bidirectional"))
      (node (ref "U1") (pin "P$84") (pinfunction "VSS_PAD_P$84") (pintype "bidirectional"))
      (node (ref "U1") (pin "P$85") (pinfunction "VSS_PAD_P$85") (pintype "bidirectional"))
      (node (ref "U1") (pin "P$86") (pinfunction "VSS_PAD_P$86") (pintype "bidirectional"))
      (node (ref "U1") (pin "P$87") (pinfunction "VSS_PAD_P$87") (pintype "bidirectional"))
      (node (ref "U1") (pin "P$88") (pinfunction "VSS_PAD_P$88") (pintype "bidirectional"))
      (node (ref "U1") (pin "P$89") (pinfunction "VSS_PAD_P$89") (pintype "bidirectional"))
      (node (ref "U1") (pin "P$90") (pinfunction "VSS_PAD_P$90") (pintype "bidirectional"))
      (node (ref "U1") (pin "P$B7") (pinfunction "VSS_P$B7") (pintype "power_in"))
      (node (ref "U1") (pin "P$F23") (pinfunction "VSS_PA_P$F23") (pintype "bidirectional"))
      (node (ref "U3") (pin "1") (pinfunction "CTG_1") (pintype "power_in"))
      (node (ref "U3") (pin "4") (pinfunction "GND_4") (pintype "power_in"))
      (node (ref "U3") (pin "6") (pinfunction "QSTRT_6") (pintype "input"))
      (node (ref "U3") (pin "9") (pinfunction "EP_9") (pintype "power_in"))
      (node (ref "X1") (pin "2") (pinfunction "2_2") (pintype "passive"))
      (node (ref "X1") (pin "4") (pinfunction "4_4") (pintype "passive"))
    )
    (net (code "18") (name "HAPTIC_EN") (class "Default")
      (node (ref "IC2") (pin "A1") (pinfunction "EN_A1") (pintype "bidirectional"))
      (node (ref "U1") (pin "P$U1") (pinfunction "P0.12_P$U1") (pintype "bidirectional"))
    )
    (net (code "19") (name "IMU_INT1") (class "Default")
      (node (ref "IC3") (pin "5") (pinfunction "INT1_5") (pintype "bidirectional"))
      (node (ref "U1") (pin "P$N1") (pinfunction "P0.08_P$N1") (pintype "bidirectional"))
    )
    (net (code "20") (name "IMU_INT2") (class "Default")
      (node (ref "IC3") (pin "6") (pinfunction "INT2_6") (pintype "bidirectional"))
      (node (ref "U1") (pin "P$P2") (pinfunction "P1.08_P$P2") (pintype "bidirectional"))
    )
    (net (code "21") (name "LX1") (class "Default")
      (node (ref "IC9") (pin "B2") (pinfunction "SW1_1_B2") (pintype "bidirectional"))
      (node (ref "IC9") (pin "B3") (pinfunction "SW1_2_B3") (pintype "bidirectional"))
      (node (ref "L7") (pin "1") (pinfunction "1_1") (pintype "bidirectional"))
    )
    (net (code "22") (name "LX2") (class "Default")
      (node (ref "IC9") (pin "D2") (pinfunction "SW2_1_D2") (pintype "bidirectional"))
      (node (ref "IC9") (pin "D3") (pinfunction "SW2_2_D3") (pintype "bidirectional"))
      (node (ref "L7") (pin "2") (pinfunction "2_2") (pintype "bidirectional"))
    )
    (net (code "23") (name "MOSI") (class "Default")
      (node (ref "J1") (pin "14") (pinfunction "14_14") (pintype "bidirectional"))
      (node (ref "U1") (pin "P$B13") (pinfunction "P0.03/AIN1_P$B13") (pintype "bidirectional"))
    )
    (net (code "24") (name "Net-(D2-K)") (class "Default")
      (node (ref "C2-EP-DR") (pin "1") (pinfunction "1_1") (pintype "passive"))
      (node (ref "D2") (pin "1") (pinfunction "K_1") (pintype "bidirectional"))
      (node (ref "D4") (pin "2") (pinfunction "A_2") (pintype "bidirectional"))
    )
    (net (code "25") (name "Net-(D5-A)") (class "Default")
      (node (ref "C2-EP-DR") (pin "2") (pinfunction "2_2") (pintype "passive"))
      (node (ref "D5") (pin "2") (pinfunction "A_2") (pintype "bidirectional"))
      (node (ref "L5") (pin "2") (pinfunction "2_2") (pintype "passive"))
      (node (ref "Q3") (pin "3") (pinfunction "D_3") (pintype "bidirectional"))
    )
    (net (code "26") (name "Net-(EPD_C1-Pad2)") (class "Default")
      (node (ref "EPD_C1") (pin "2") (pinfunction "2_2") (pintype "passive"))
      (node (ref "J1") (pin "5") (pinfunction "5_5") (pintype "bidirectional"))
    )
    (net (code "27") (name "Net-(EPD_C2-Pad2)") (class "Default")
      (node (ref "EPD_C2") (pin "2") (pinfunction "2_2") (pintype "passive"))
      (node (ref "J1") (pin "4") (pinfunction "4_4") (pintype "bidirectional"))
    )
    (net (code "28") (name "Net-(EPD_C6-Pad2)") (class "Default")
      (node (ref "EPD_C6") (pin "2") (pinfunction "2_2") (pintype "passive"))
      (node (ref "J1") (pin "18") (pinfunction "18_18") (pintype "bidirectional"))
    )
    (net (code "29") (name "Net-(EPD_C7-Pad2)") (class "Default")
      (node (ref "EPD_C7") (pin "2") (pinfunction "2_2") (pintype "passive"))
      (node (ref "J1") (pin "19") (pinfunction "19_19") (pintype "bidirectional"))
    )
    (net (code "30") (name "Net-(EPD_C8-Pad2)") (class "Default")
      (node (ref "EPD_C8") (pin "2") (pinfunction "2_2") (pintype "passive"))
      (node (ref "J1") (pin "20") (pinfunction "20_20") (pintype "bidirectional"))
    )
    (net (code "31") (name "Net-(EPD_C10-Pad2)") (class "Default")
      (node (ref "EPD_C10") (pin "2") (pinfunction "2_2") (pintype "passive"))
      (node (ref "J1") (pin "22") (pinfunction "22_22") (pintype "bidirectional"))
    )
    (net (code "32") (name "Net-(EPD_C12-Pad2)") (class "Default")
      (node (ref "EPD_C12") (pin "2") (pinfunction "2_2") (pintype "passive"))
      (node (ref "J1") (pin "24") (pinfunction "24_24") (pintype "bidirectional"))
    )
    (net (code "33") (name "Net-(IC1-TS{slash}MR)") (class "Default")
      (node (ref "IC1") (pin "D1") (pinfunction "TS/MR_D1") (pintype "bidirectional"))
      (node (ref "R9") (pin "2") (pinfunction "2_2") (pintype "bidirectional"))
    )
    (net (code "34") (name "Net-(IC2-REG)") (class "Default")
      (node (ref "C32") (pin "2") (pinfunction "2_2") (pintype "passive"))
      (node (ref "IC2") (pin "A2") (pinfunction "REG_A2") (pintype "bidirectional"))
    )
    (net (code "35") (name "Net-(IC3-SDO)") (class "Default")
      (node (ref "IC3") (pin "1") (pinfunction "SDO_1") (pintype "bidirectional"))
      (node (ref "R3") (pin "2") (pinfunction "2_2") (pintype "bidirectional"))
    )
    (net (code "36") (name "Net-(IC9-SCL)") (class "Default")
      (node (ref "IC9") (pin "D1") (pinfunction "SCL_D1") (pintype "bidirectional"))
      (node (ref "R4") (pin "2") (pinfunction "2_2") (pintype "bidirectional"))
    )
    (net (code "37") (name "Net-(IC9-SDA)") (class "Default")
      (node (ref "IC9") (pin "E1") (pinfunction "SDA_E1") (pintype "bidirectional"))
      (node (ref "R2") (pin "2") (pinfunction "2_2") (pintype "bidirectional"))
    )
    (net (code "38") (name "Net-(J4-CC1)") (class "Default")
      (node (ref "J4") (pin "A5") (pinfunction "CC1_A5") (pintype "bidirectional"))
      (node (ref "R1_USB") (pin "2") (pinfunction "2_2") (pintype "bidirectional"))
    )
    (net (code "39") (name "Net-(J4-CC2)") (class "Default")
      (node (ref "J4") (pin "B5") (pinfunction "CC2_B5") (pintype "bidirectional"))
      (node (ref "R2_USB") (pin "1") (pinfunction "1_1") (pintype "bidirectional"))
    )
    (net (code "40") (name "Net-(L2-Pad2)") (class "Default")
      (node (ref "L2") (pin "2") (pinfunction "2_2") (pintype "passive"))
      (node (ref "L3") (pin "1") (pinfunction "1_1") (pintype "passive"))
    )
    (net (code "41") (name "Net-(R1_EP_DR-Pad1)") (class "Default")
      (node (ref "R1_EP_DR") (pin "1") (pinfunction "1_1") (pintype "bidirectional"))
      (node (ref "R_TYPE_SEL") (pin "2") (pinfunction "2_2") (pintype "bidirectional"))
      (node (ref "SJ1") (pin "2") (pinfunction "2_2") (pintype "passive"))
    )
    (net (code "42") (name "Net-(U1-ANT)") (class "Default")
      (node (ref "C3") (pin "1") (pinfunction "1_1") (pintype "passive"))
      (node (ref "L1") (pin "1") (pinfunction "1_1") (pintype "passive"))
      (node (ref "U1") (pin "P$H23") (pinfunction "ANT_P$H23") (pintype "bidirectional"))
    )
    (net (code "43") (name "Net-(U1-DCC)") (class "Default")
      (node (ref "L2") (pin "1") (pinfunction "1_1") (pintype "passive"))
      (node (ref "U1") (pin "P$B3") (pinfunction "DCC_P$B3") (pintype "output"))
    )
    (net (code "44") (name "Net-(U1-DEC2)") (class "Default")
      (node (ref "C13") (pin "1") (pinfunction "1_1") (pintype "passive"))
      (node (ref "U1") (pin "P$A18") (pinfunction "DEC2_P$A18") (pintype "bidirectional"))
    )
    (net (code "45") (name "Net-(U1-DEC3V3)") (class "Default")
      (node (ref "C20") (pin "1") (pinfunction "1_1") (pintype "passive"))
      (node (ref "U1") (pin "P$AC5") (pinfunction "DEC3V3_P$AC5") (pintype "bidirectional"))
    )
    (net (code "46") (name "Net-(U1-DEC5)") (class "Default")
      (node (ref "C9") (pin "1") (pinfunction "1_1") (pintype "passive"))
      (node (ref "U1") (pin "P$N24") (pinfunction "DEC5_P$N24") (pintype "bidirectional"))
    )
    (net (code "47") (name "Net-(U1-XC1)") (class "Default")
      (node (ref "C1") (pin "1") (pinfunction "1_1") (pintype "passive"))
      (node (ref "U1") (pin "P$B24") (pinfunction "XC1_P$B24") (pintype "input"))
      (node (ref "X1") (pin "1") (pinfunction "1_1") (pintype "passive"))
    )
    (net (code "48") (name "Net-(U1-XC2)") (class "Default")
      (node (ref "C2") (pin "1") (pinfunction "1_1") (pintype "passive"))
      (node (ref "U1") (pin "P$A23") (pinfunction "XC2_P$A23") (pintype "output"))
      (node (ref "X1") (pin "3") (pinfunction "3_3") (pintype "passive"))
    )
    (net (code "49") (name "OUT+") (class "Default")
      (node (ref "IC2") (pin "A3") (pinfunction "OUT+_A3") (pintype "bidirectional"))
      (node (ref "TP_OP") (pin "TP") (pinfunction "TP_TP") (pintype "input"))
    )
    (net (code "50") (name "OUT-") (class "Default")
      (node (ref "IC2") (pin "C3") (pinfunction "OUT-_C3") (pintype "bidirectional"))
      (node (ref "TP_ON") (pin "TP") (pinfunction "TP_TP") (pintype "input"))
    )
    (net (code "51") (name "P0.00{slash}XL1") (class "Default")
      (node (ref "C17") (pin "2") (pinfunction "2_2") (pintype "passive"))
      (node (ref "U1") (pin "P$D2") (pinfunction "P0.00/XL1_P$D2") (pintype "bidirectional"))
      (node (ref "X2") (pin "1") (pinfunction "1_1") (pintype "passive"))
    )
    (net (code "52") (name "P0.01{slash}XL2") (class "Default")
      (node (ref "C18") (pin "2") (pinfunction "2_2") (pintype "passive"))
      (node (ref "U1") (pin "P$F2") (pinfunction "P0.01/XL2_P$F2") (pintype "bidirectional"))
      (node (ref "X2") (pin "2") (pinfunction "2_2") (pintype "passive"))
    )
    (net (code "53") (name "P0.04") (class "Default")
      (node (ref "U1") (pin "P$J1") (pinfunction "P0.04/AIN2_P$J1") (pintype "bidirectional"))
    )
    (net (code "54") (name "P0.09") (class "Default")
      (node (ref "U1") (pin "P$L24") (pinfunction "P0.09/NFC1_P$L24") (pintype "bidirectional"))
    )
    (net (code "55") (name "P0.13") (class "Default")
      (node (ref "C30") (pin "2") (pinfunction "2_2") (pintype "passive"))
      (node (ref "R5") (pin "1") (pinfunction "1_1") (pintype "bidirectional"))
      (node (ref "SW_UP") (pin "2") (pinfunction "2_2") (pintype "passive"))
      (node (ref "U1") (pin "P$AD8") (pinfunction "P0.13_P$AD8") (pintype "bidirectional"))
    )
    (net (code "56") (name "P0.14") (class "Default")
      (node (ref "C31") (pin "2") (pinfunction "2_2") (pintype "passive"))
      (node (ref "R8") (pin "1") (pinfunction "1_1") (pintype "bidirectional"))
      (node (ref "SW_ENT") (pin "2") (pinfunction "2_2") (pintype "passive"))
      (node (ref "U1") (pin "P$AC9") (pinfunction "P0.14_P$AC9") (pintype "bidirectional"))
    )
    (net (code "57") (name "P0.19") (class "Default")
      (node (ref "U1") (pin "P$AC15") (pinfunction "P0.19_P$AC15") (pintype "bidirectional"))
    )
    (net (code "58") (name "P0.20") (class "Default")
      (node (ref "U1") (pin "P$AD16") (pinfunction "P0.20_P$AD16") (pintype "bidirectional"))
    )
    (net (code "59") (name "P0.21") (class "Default")
      (node (ref "U1") (pin "P$AC17") (pinfunction "P0.21_P$AC17") (pintype "bidirectional"))
    )
    (net (code "60") (name "P0.22") (class "Default")
      (node (ref "U1") (pin "P$AD18") (pinfunction "P0.22_P$AD18") (pintype "bidirectional"))
    )
    (net (code "61") (name "P0.23") (class "Default")
      (node (ref "U1") (pin "P$AC19") (pinfunction "P0.23_P$AC19") (pintype "bidirectional"))
    )
    (net (code "62") (name "P0.24") (class "Default")
      (node (ref "U1") (pin "P$AD20") (pinfunction "P0.24_P$AD20") (pintype "bidirectional"))
    )
    (net (code "63") (name "P0.25") (class "Default")
      (node (ref "U1") (pin "P$AC21") (pinfunction "P0.25_P$AC21") (pintype "bidirectional"))
    )
    (net (code "64") (name "P0.26") (class "Default")
      (node (ref "U1") (pin "P$G1") (pinfunction "P0.26_P$G1") (pintype "bidirectional"))
    )
    (net (code "65") (name "P0.27") (class "Default")
      (node (ref "U1") (pin "P$H2") (pinfunction "P0.27_P$H2") (pintype "bidirectional"))
    )
    (net (code "66") (name "P0.28") (class "Default")
      (node (ref "U1") (pin "P$B11") (pinfunction "P0.28/AIN4_P$B11") (pintype "bidirectional"))
    )
    (net (code "67") (name "P0.29") (class "Default")
      (node (ref "U1") (pin "P$A10") (pinfunction "P0.29/AIN5_P$A10") (pintype "bidirectional"))
    )
    (net (code "68") (name "P0.30") (class "Default")
      (node (ref "U1") (pin "P$B9") (pinfunction "P0.30/AIN6_P$B9") (pintype "bidirectional"))
    )
    (net (code "69") (name "P0.31") (class "Default")
      (node (ref "U1") (pin "P$A8") (pinfunction "P0.31/AIN7_P$A8") (pintype "bidirectional"))
    )
    (net (code "70") (name "P1.01") (class "Default")
      (node (ref "Q1") (pin "1") (pinfunction "G_1") (pintype "bidirectional"))
      (node (ref "R_PWR_EPD") (pin "1") (pinfunction "1_1") (pintype "bidirectional"))
      (node (ref "U1") (pin "P$Y23") (pinfunction "P1.01_P$Y23") (pintype "bidirectional"))
    )
    (net (code "71") (name "P1.02") (class "Default")
      (node (ref "C29") (pin "2") (pinfunction "2_2") (pintype "passive"))
      (node (ref "R7") (pin "1") (pinfunction "1_1") (pintype "bidirectional"))
      (node (ref "SW_DN") (pin "2") (pinfunction "2_2") (pintype "passive"))
      (node (ref "U1") (pin "P$W24") (pinfunction "P1.02_P$W24") (pintype "bidirectional"))
    )
    (net (code "72") (name "P1.03") (class "Default")
      (node (ref "U1") (pin "P$V23") (pinfunction "P1.03_P$V23") (pintype "bidirectional"))
    )
    (net (code "73") (name "P1.04") (class "Default")
      (node (ref "U1") (pin "P$U24") (pinfunction "P1.04_P$U24") (pintype "bidirectional"))
    )
    (net (code "74") (name "P1.05") (class "Default")
      (node (ref "U1") (pin "P$T23") (pinfunction "P1.05_P$T23") (pintype "bidirectional"))
    )
    (net (code "75") (name "P1.06") (class "Default")
      (node (ref "U1") (pin "P$R24") (pinfunction "P1.06_P$R24") (pintype "bidirectional"))
    )
    (net (code "76") (name "P1.07") (class "Default")
      (node (ref "U1") (pin "P$P23") (pinfunction "P1.07_P$P23") (pintype "bidirectional"))
    )
    (net (code "77") (name "P1.09") (class "Default")
      (node (ref "U1") (pin "P$R1") (pinfunction "P1.09_P$R1") (pintype "bidirectional"))
    )
    (net (code "78") (name "P1.10") (class "Default")
      (node (ref "U1") (pin "P$A20") (pinfunction "P1.10_P$A20") (pintype "bidirectional"))
    )
    (net (code "79") (name "P1.11") (class "Default")
      (node (ref "U1") (pin "P$B19") (pinfunction "P1.11_P$B19") (pintype "bidirectional"))
    )
    (net (code "80") (name "P1.12") (class "Default")
      (node (ref "U1") (pin "P$B17") (pinfunction "P1.12_P$B17") (pintype "bidirectional"))
    )
    (net (code "81") (name "P1.13") (class "Default")
      (node (ref "U1") (pin "P$A16") (pinfunction "P1.13_P$A16") (pintype "bidirectional"))
    )
    (net (code "82") (name "P1.14") (class "Default")
      (node (ref "U1") (pin "P$B15") (pinfunction "P1.14_P$B15") (pintype "bidirectional"))
    )
    (net (code "83") (name "P1.15") (class "Default")
      (node (ref "U1") (pin "P$A14") (pinfunction "P1.15_P$A14") (pintype "bidirectional"))
    )
    (net (code "84") (name "PMIC_INT") (class "Default")
      (node (ref "IC1") (pin "A1") (pinfunction "~{INT}_A1") (pintype "bidirectional"))
      (node (ref "U1") (pin "P$T2") (pinfunction "P0.11_P$T2") (pintype "bidirectional"))
    )
    (net (code "85") (name "PREVGH") (class "Default")
      (node (ref "D5") (pin "1") (pinfunction "K_1") (pintype "bidirectional"))
      (node (ref "EPD_C9") (pin "2") (pinfunction "2_2") (pintype "passive"))
      (node (ref "J1") (pin "21") (pinfunction "21_21") (pintype "bidirectional"))
    )
    (net (code "86") (name "PREVGL") (class "Default")
      (node (ref "D2") (pin "2") (pinfunction "A_2") (pintype "bidirectional"))
      (node (ref "EPD_C11") (pin "2") (pinfunction "2_2") (pintype "passive"))
      (node (ref "J1") (pin "23") (pinfunction "23_23") (pintype "bidirectional"))
    )
    (net (code "87") (name "RESE") (class "Default")
      (node (ref "J1") (pin "3") (pinfunction "3_3") (pintype "bidirectional"))
      (node (ref "Q3") (pin "2") (pinfunction "S_2") (pintype "bidirectional"))
      (node (ref "R1_EP_DR") (pin "2") (pinfunction "2_2") (pintype "bidirectional"))
    )
    (net (code "88") (name "RESET") (class "Default")
      (node (ref "J2") (pin "6") (pinfunction "6_6") (pintype "bidirectional"))
      (node (ref "TP_RESET") (pin "TP") (pinfunction "TP_TP") (pintype "input"))
      (node (ref "U1") (pin "P$AC13") (pinfunction "P0.18/RESET_P$AC13") (pintype "bidirectional"))
    )
    (net (code "89") (name "RF") (class "Default")
      (node (ref "ANT1") (pin "1") (pinfunction "FEED_1") (pintype "input"))
      (node (ref "C22") (pin "1") (pinfunction "1_1") (pintype "passive"))
      (node (ref "C4") (pin "1") (pinfunction "1_1") (pintype "passive"))
      (node (ref "L1") (pin "2") (pinfunction "2_2") (pintype "passive"))
    )
    (net (code "90") (name "SCK") (class "Default")
      (node (ref "J1") (pin "13") (pinfunction "13_13") (pintype "bidirectional"))
      (node (ref "U1") (pin "P$A12") (pinfunction "P0.02/AIN0_P$A12") (pintype "bidirectional"))
    )
    (net (code "91") (name "SCL{slash}1.4C") (class "Default")
      (node (ref "IC2") (pin "C1") (pinfunction "SCL_C1") (pintype "bidirectional"))
      (node (ref "U3") (pin "7") (pinfunction "SCL_7") (pintype "input"))
    )
    (net (code "92") (name "SCL{slash}2.4C") (class "Default")
      (node (ref "IC1") (pin "B1") (pinfunction "SCL_B1") (pintype "bidirectional"))
      (node (ref "IC3") (pin "12") (pinfunction "SCX_12") (pintype "bidirectional"))
      (node (ref "R17") (pin "2") (pinfunction "2_2") (pintype "bidirectional"))
      (node (ref "R4") (pin "1") (pinfunction "1_1") (pintype "bidirectional"))
      (node (ref "TP_SCL") (pin "TP") (pinfunction "TP_TP") (pintype "input"))
      (node (ref "U1") (pin "P$M2") (pinfunction "P0.07_P$M2") (pintype "bidirectional"))
    )
    (net (code "93") (name "SDA{slash}1.4C") (class "Default")
      (node (ref "IC2") (pin "B2") (pinfunction "SDA_B2") (pintype "bidirectional"))
      (node (ref "U3") (pin "8") (pinfunction "SDA_8") (pintype "bidirectional"))
    )
    (net (code "94") (name "SDA{slash}2.4C") (class "Default")
      (node (ref "IC1") (pin "C1") (pinfunction "SDA_C1") (pintype "bidirectional"))
      (node (ref "IC3") (pin "2") (pinfunction "SDX_2") (pintype "bidirectional"))
      (node (ref "R18") (pin "2") (pinfunction "2_2") (pintype "bidirectional"))
      (node (ref "R2") (pin "1") (pinfunction "1_1") (pintype "bidirectional"))
      (node (ref "TP_SDA") (pin "TP") (pinfunction "TP_TP") (pintype "input"))
      (node (ref "U1") (pin "P$L1") (pinfunction "P0.06_P$L1") (pintype "bidirectional"))
    )
    (net (code "95") (name "SWDCLK") (class "Default")
      (node (ref "J2") (pin "4") (pinfunction "4_4") (pintype "bidirectional"))
      (node (ref "TP_SWDCLK") (pin "TP") (pinfunction "TP_TP") (pintype "input"))
      (node (ref "U1") (pin "P$AA24") (pinfunction "SWDCLK_P$AA24") (pintype "input"))
    )
    (net (code "96") (name "SWDIO") (class "Default")
      (node (ref "J2") (pin "2") (pinfunction "2_2") (pintype "bidirectional"))
      (node (ref "TP_SWDIO") (pin "TP") (pinfunction "TP_TP") (pintype "input"))
      (node (ref "U1") (pin "P$AC24") (pinfunction "SWDIO_P$AC24") (pintype "bidirectional"))
    )
    (net (code "97") (name "SWO") (class "Default")
      (node (ref "TP_SWO") (pin "TP") (pinfunction "TP_TP") (pintype "input"))
      (node (ref "U1") (pin "P$AD22") (pinfunction "P1.00_P$AD22") (pintype "bidirectional"))
    )
    (net (code "98") (name "VBAT{slash}1.2A") (class "Default")
      (node (ref "C27") (pin "2") (pinfunction "2_2") (pintype "passive"))
      (node (ref "TP_VBAT") (pin "TP") (pinfunction "TP_TP") (pintype "input"))
      (node (ref "U3") (pin "2") (pinfunction "CELL_2") (pintype "power_in"))
      (node (ref "U3") (pin "3") (pinfunction "VDD_3") (pintype "power_in"))
    )
    (net (code "99") (name "VBAT{slash}2.5C") (class "Default")
      (node (ref "C37") (pin "2") (pinfunction "2_2") (pintype "passive"))
      (node (ref "IC1") (pin "C2") (pinfunction "BAT_C2") (pintype "bidirectional"))
    )
    (net (code "100") (name "VBUS{slash}1.5D") (class "Default")
      (node (ref "C42") (pin "1") (pinfunction "1_1") (pintype "passive"))
      (node (ref "C43") (pin "1") (pinfunction "1_1") (pintype "passive"))
      (node (ref "D3") (pin "5") (pinfunction "VBUS_5") (pintype "bidirectional"))
      (node (ref "J4") (pin "A4_B9") (pinfunction "VBUS_A4_B9") (pintype "power_in"))
      (node (ref "J4") (pin "A9_B4") (pinfunction "VBUS_A9_B4") (pintype "power_in"))
    )
    (net (code "101") (name "VBUS{slash}2.6D") (class "Default")
      (node (ref "C21") (pin "1") (pinfunction "1_1") (pintype "passive"))
      (node (ref "C38") (pin "2") (pinfunction "2_2") (pintype "passive"))
      (node (ref "IC1") (pin "A2") (pinfunction "IN_A2") (pintype "bidirectional"))
      (node (ref "U1") (pin "P$AD2") (pinfunction "VBUS_P$AD2") (pintype "power_in"))
    )
    (net (code "102") (name "VREG") (class "Default")
      (node (ref "C23") (pin "1") (pinfunction "1_1") (pintype "passive"))
      (node (ref "C24") (pin "2") (pinfunction "2_2") (pintype "passive"))
      (node (ref "C39") (pin "1") (pinfunction "1_1") (pintype "passive"))
      (node (ref "IC1") (pin "B2") (pinfunction "SYS_B2") (pintype "bidirectional"))
      (node (ref "IC9") (pin "A1") (pinfunction "EN_A1") (pintype "bidirectional"))
      (node (ref "IC9") (pin "A2") (pinfunction "VIN_1_A2") (pintype "bidirectional"))
      (node (ref "IC9") (pin "A3") (pinfunction "VIN_2_A3") (pintype "bidirectional"))
      (node (ref "TP_VREG") (pin "TP") (pinfunction "TP_TP") (pintype "input"))
    )
    (net (code "103") (name "unconnected-(ANT1-NC-Pad2)") (class "Default")
      (node (ref "ANT1") (pin "2") (pinfunction "NC_2") (pintype "no_connect"))
    )
    (net (code "104") (name "unconnected-(IC3-ASCL-Pad11)") (class "Default")
      (node (ref "IC3") (pin "11") (pinfunction "ASCL_11") (pintype "bidirectional"))
    )
    (net (code "105") (name "unconnected-(IC3-ASDA-Pad4)") (class "Default")
      (node (ref "IC3") (pin "4") (pinfunction "ASDA_4") (pintype "bidirectional"))
    )
    (net (code "106") (name "unconnected-(J1-Pad1)") (class "Default")
      (node (ref "J1") (pin "1") (pinfunction "1_1") (pintype "bidirectional"))
    )
    (net (code "107") (name "unconnected-(J1-Pad6)") (class "Default")
      (node (ref "J1") (pin "6") (pinfunction "6_6") (pintype "bidirectional"))
    )
    (net (code "108") (name "unconnected-(J1-Pad7)") (class "Default")
      (node (ref "J1") (pin "7") (pinfunction "7_7") (pintype "bidirectional"))
    )
    (net (code "109") (name "unconnected-(J4-SBU1-PadA8)") (class "Default")
      (node (ref "J4") (pin "A8") (pinfunction "SBU1_A8") (pintype "bidirectional"))
    )
    (net (code "110") (name "unconnected-(J4-SBU2-PadB8)") (class "Default")
      (node (ref "J4") (pin "B8") (pinfunction "SBU2_B8") (pintype "bidirectional"))
    )
    (net (code "111") (name "unconnected-(R7-Pad2)") (class "Default")
      (node (ref "R7") (pin "2") (pinfunction "2_2") (pintype "bidirectional"))
    )
    (net (code "112") (name "unconnected-(R8-Pad2)") (class "Default")
      (node (ref "R8") (pin "2") (pinfunction "2_2") (pintype "bidirectional"))
    )
    (net (code "113") (name "unconnected-(U1-DCCH-PadP$AB2)") (class "Default")
      (node (ref "U1") (pin "P$AB2") (pinfunction "DCCH_P$AB2") (pintype "bidirectional"))
    )
  )
)
